# Reference_Voltage_2V048.net
KiCad netlist of a schematic drawn in Altium Designer
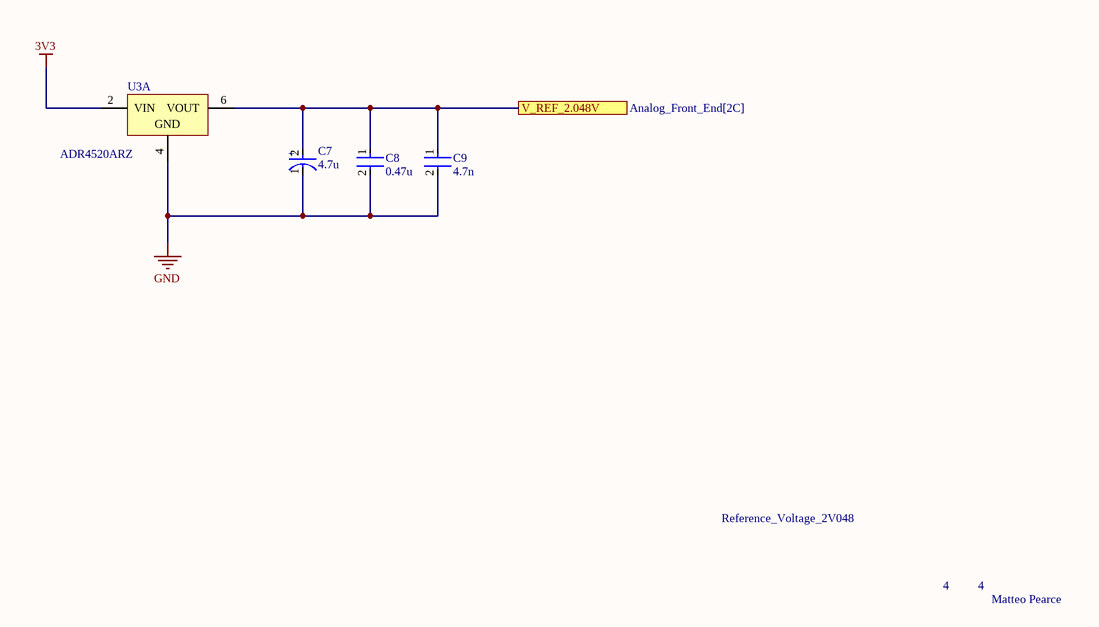
[diagram p0: Reference_Voltage_2V048.SchDoc]

(export (version "E")
  (design (tool "Eeschema 10.0.6"))
  (components
    (comp (ref "C7")
      (value "4.7u")
      (footprint "FP-TAJA-MFG")
      (description "4.7uF 20V  ±10% 4Ω 1206  SMD Tantalum Capacitor")
      (fields (field (name "TOLERANCE") "10%") (field (name "VOLTAGE") "20V"))
      (libsource (lib "Altium Content Vault") (part "203bc49f2ac43e59fd269a8c329ed05"))
    )
    (comp (ref "C8")
      (value "0.47u")
      (footprint "FP-GCM188-0_1-IPC_A")
      (description "Ceramic Capacitor for Automotive 470nF  ±10% 16VDC X7R 0603 Paper T/R")
      (fields (field (name "VOLTAGE") "16V") (field (name "TOLERANCE") "10%"))
      (libsource (lib "Altium Content Vault") (part "02cd4be3c70576c341d710602a673aa"))
    )
    (comp (ref "C9")
      (value "4.7n")
      (footprint "FP-CC0805-0_85-MFG")
      (description "CC0805 47 nF X7R 10.00% 50 V")
      (fields (field (name "MANUFACTURER PART NUMBER") "CC0805KRX7R9BB473"))
      (libsource (lib "Altium Content Vault") (part "11868f565c42a9108669ba33697ecf6"))
    )
    (comp (ref "U3")
      (value "ADR4520ARZ")
      (footprint "ADI-R-8_M")
      (fields (field (name "MANUFACTURER") "Analog Devices"))
      (libsource (lib "Altium Content Vault") (part "ADI-ADR45xx-R-8"))
    )
  )
  (nets
    (net (code "1") (name "/V_REF_2.048V") (class "Default")
      (node (ref "C7") (pin "2") (pinfunction "A_2") (pintype "passive"))
      (node (ref "C8") (pin "1") (pinfunction "1_1") (pintype "passive"))
      (node (ref "C9") (pin "1") (pinfunction "1_1") (pintype "passive"))
      (node (ref "U3") (pin "6") (pinfunction "VOUT_6") (pintype "power_in"))
    )
    (net (code "2") (name "3V3") (class "Default")
      (node (ref "U3") (pin "2") (pinfunction "VIN_2") (pintype "power_in"))
    )
    (net (code "3") (name "GND") (class "Default")
      (node (ref "C7") (pin "1") (pinfunction "C_1") (pintype "passive"))
      (node (ref "C8") (pin "2") (pinfunction "2_2") (pintype "passive"))
      (node (ref "C9") (pin "2") (pinfunction "2_2") (pintype "passive"))
      (node (ref "U3") (pin "4") (pinfunction "GND_4") (pintype "power_in"))
    )
  )
)
